# 11-MT7688AN_RF_Front_End.net
KiCad netlist of a schematic drawn in Altium Designer
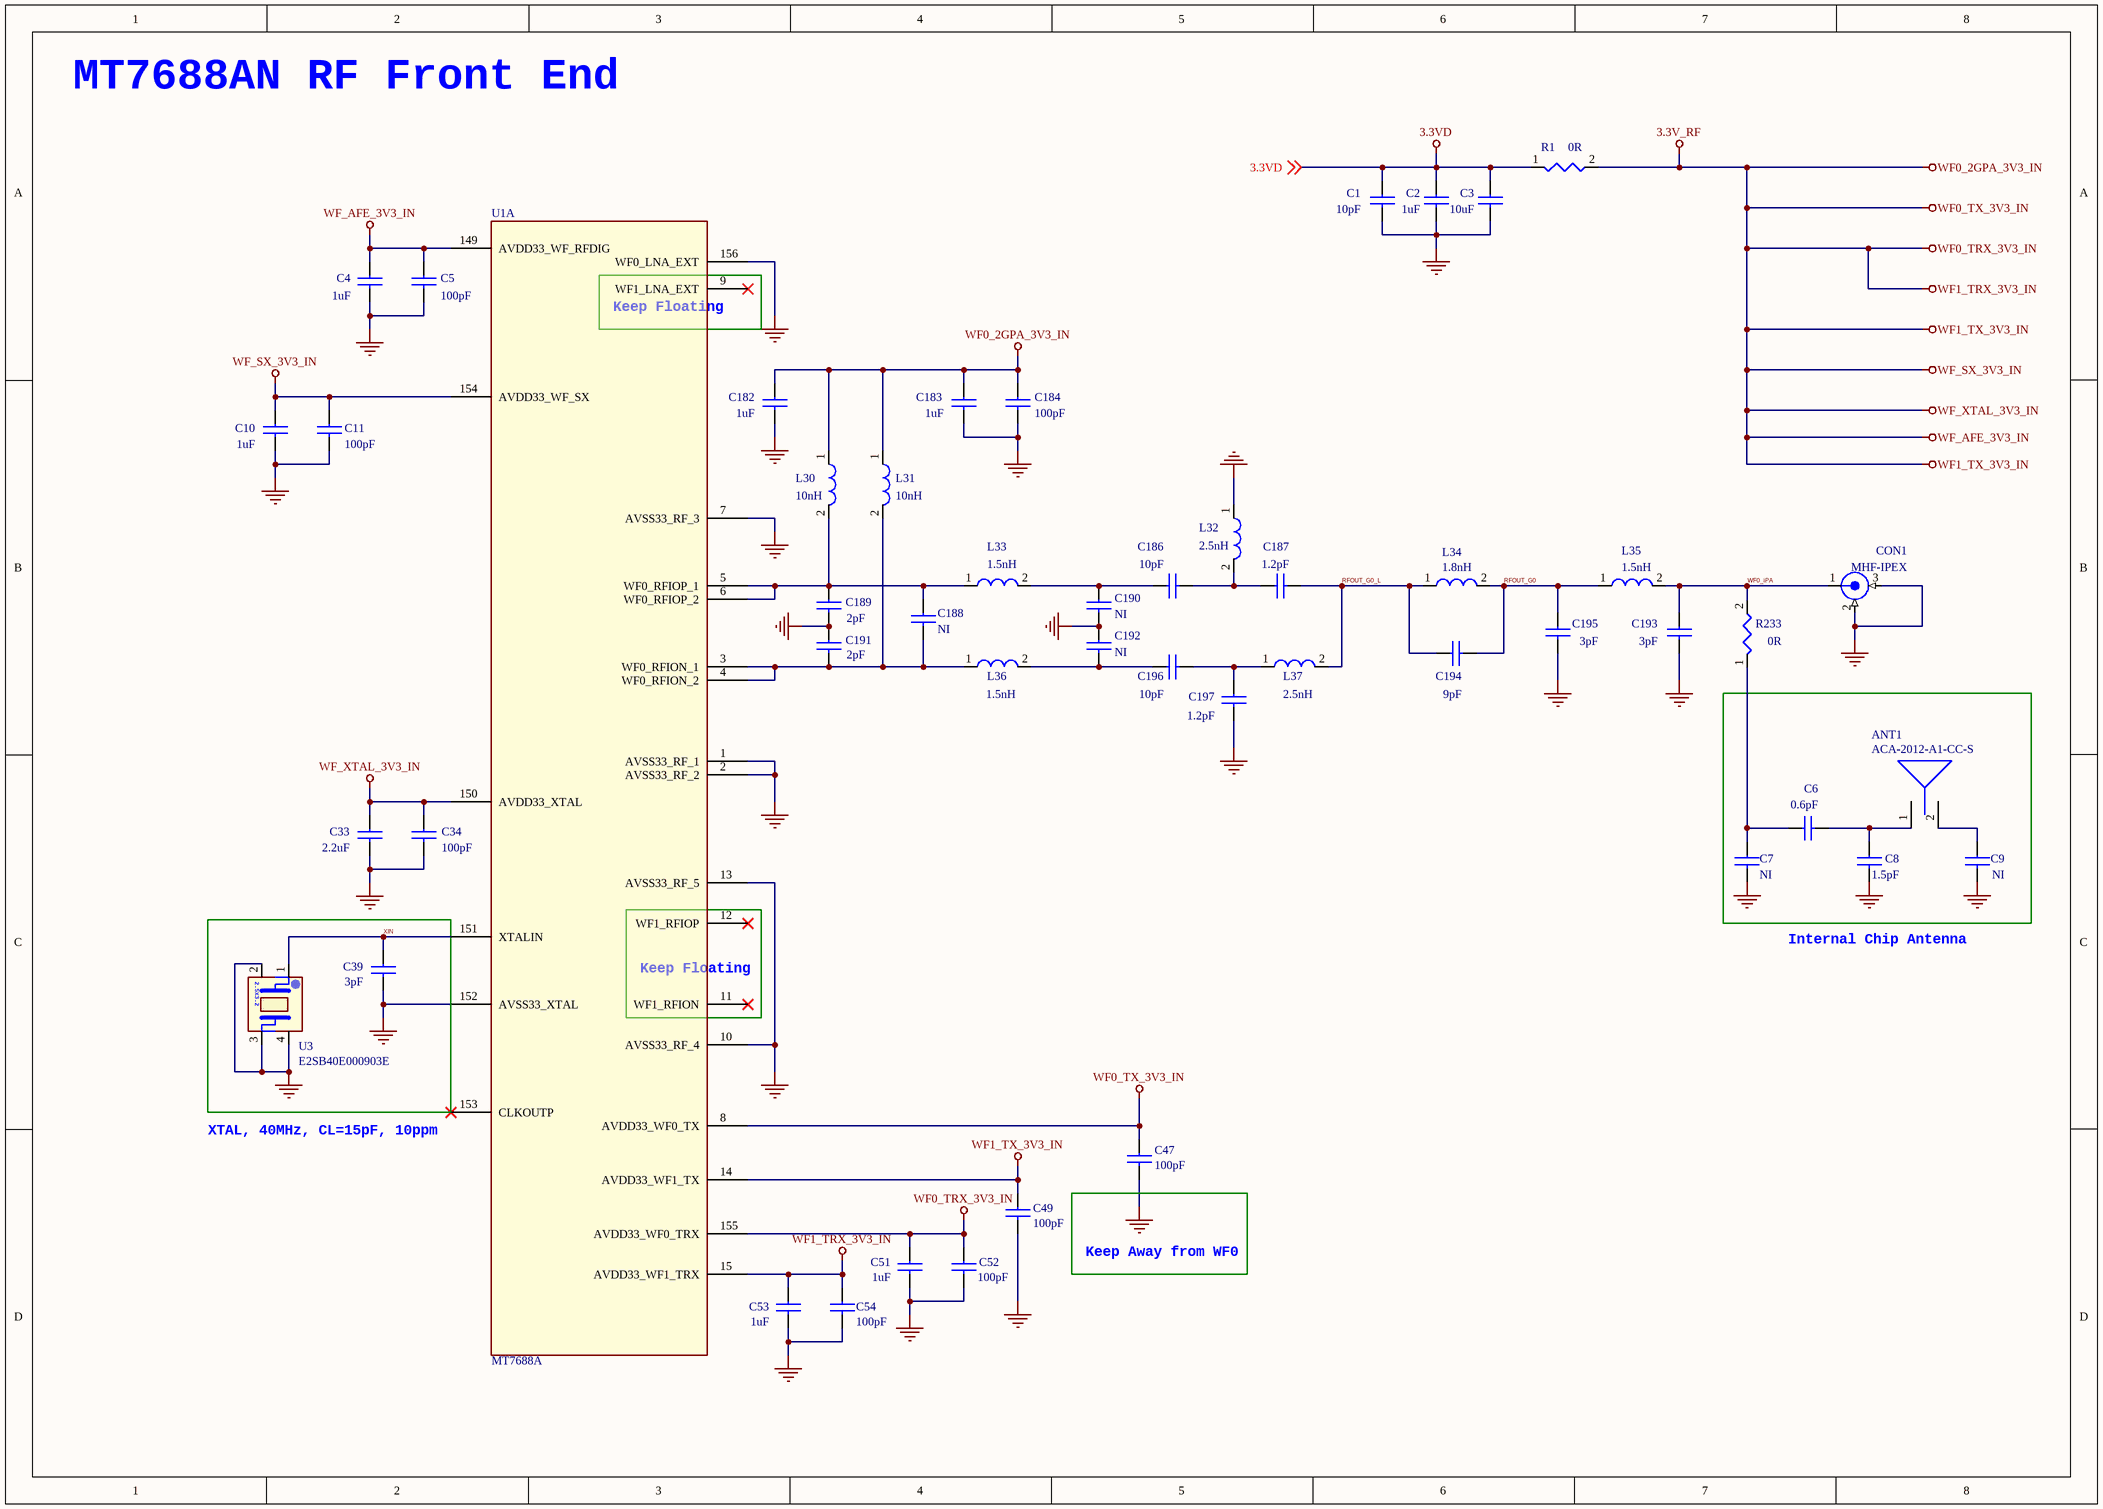
[diagram p0: 11-MT7688AN RF Front End.SchDoc]

(export (version "E")
  (design (tool "Eeschema 10.0.6"))
  (components
    (comp (ref "ANT1")
      (value "ACA-2012-A1-CC-S")
      (footprint "ACA-2012A")
      (libsource (lib "LinkIt Air+ (EK-7688AM+)") (part "Antenna_2012"))
    )
    (comp (ref "C1")
      (value "10pF")
      (footprint "RLC 0201 M35")
      (libsource (lib "LinkIt Air+ (EK-7688AM+)") (part "CAP NP"))
    )
    (comp (ref "C2")
      (value "1uF")
      (footprint "RLC 0201 M35")
      (libsource (lib "LinkIt Air+ (EK-7688AM+)") (part "CAP NP"))
    )
    (comp (ref "C3")
      (value "10uF")
      (footprint "RLC 0402 M35")
      (libsource (lib "LinkIt Air+ (EK-7688AM+)") (part "CAP NP"))
    )
    (comp (ref "C4")
      (value "1uF")
      (footprint "RLC 0201 M35")
      (libsource (lib "LinkIt Air+ (EK-7688AM+)") (part "CAP NP"))
    )
    (comp (ref "C5")
      (value "100pF")
      (footprint "RLC 0201 M35")
      (libsource (lib "LinkIt Air+ (EK-7688AM+)") (part "CAP NP"))
    )
    (comp (ref "C6")
      (value "0.6pF")
      (footprint "RLC 0201 M35")
      (libsource (lib "LinkIt Air+ (EK-7688AM+)") (part "CAP NP"))
    )
    (comp (ref "C7")
      (value "NI")
      (footprint "RLC 0201 M35")
      (libsource (lib "LinkIt Air+ (EK-7688AM+)") (part "CAP NP"))
    )
    (comp (ref "C8")
      (value "1.5pF")
      (footprint "RLC 0201 M35")
      (libsource (lib "LinkIt Air+ (EK-7688AM+)") (part "CAP NP"))
    )
    (comp (ref "C9")
      (value "NI")
      (footprint "RLC 0402 M35")
      (libsource (lib "LinkIt Air+ (EK-7688AM+)") (part "CAP NP"))
    )
    (comp (ref "C10")
      (value "1uF")
      (footprint "RLC 0201 M35")
      (libsource (lib "LinkIt Air+ (EK-7688AM+)") (part "CAP NP"))
    )
    (comp (ref "C11")
      (value "100pF")
      (footprint "RLC 0201 M35")
      (libsource (lib "LinkIt Air+ (EK-7688AM+)") (part "CAP NP"))
    )
    (comp (ref "C33")
      (value "2.2uF")
      (footprint "RLC 0402 M35")
      (libsource (lib "LinkIt Air+ (EK-7688AM+)") (part "CAP NP"))
    )
    (comp (ref "C34")
      (value "100pF")
      (footprint "RLC 0201 M35")
      (libsource (lib "LinkIt Air+ (EK-7688AM+)") (part "CAP NP"))
    )
    (comp (ref "C39")
      (value "3pF")
      (footprint "RLC 0201 M35")
      (libsource (lib "LinkIt Air+ (EK-7688AM+)") (part "CAP NP"))
    )
    (comp (ref "C47")
      (value "100pF")
      (footprint "RLC 0201 M35")
      (libsource (lib "LinkIt Air+ (EK-7688AM+)") (part "CAP NP"))
    )
    (comp (ref "C49")
      (value "100pF")
      (footprint "RLC 0201 M35")
      (libsource (lib "LinkIt Air+ (EK-7688AM+)") (part "CAP NP"))
    )
    (comp (ref "C51")
      (value "1uF")
      (footprint "RLC 0201 M35")
      (libsource (lib "LinkIt Air+ (EK-7688AM+)") (part "CAP NP"))
    )
    (comp (ref "C52")
      (value "100pF")
      (footprint "RLC 0201 M35")
      (libsource (lib "LinkIt Air+ (EK-7688AM+)") (part "CAP NP"))
    )
    (comp (ref "C53")
      (value "1uF")
      (footprint "RLC 0201 M35")
      (libsource (lib "LinkIt Air+ (EK-7688AM+)") (part "CAP NP"))
    )
    (comp (ref "C54")
      (value "100pF")
      (footprint "RLC 0201 M35")
      (libsource (lib "LinkIt Air+ (EK-7688AM+)") (part "CAP NP"))
    )
    (comp (ref "C182")
      (value "1uF")
      (footprint "RLC 0201 M35")
      (libsource (lib "LinkIt Air+ (EK-7688AM+)") (part "CAP NP"))
    )
    (comp (ref "C183")
      (value "1uF")
      (footprint "RLC 0201 M35")
      (libsource (lib "LinkIt Air+ (EK-7688AM+)") (part "CAP NP"))
    )
    (comp (ref "C184")
      (value "100pF")
      (footprint "RLC 0201 M35")
      (libsource (lib "LinkIt Air+ (EK-7688AM+)") (part "CAP NP"))
    )
    (comp (ref "C186")
      (value "10pF")
      (footprint "RLC 0201 M35")
      (libsource (lib "LinkIt Air+ (EK-7688AM+)") (part "CAP NP"))
    )
    (comp (ref "C187")
      (value "1.2pF")
      (footprint "RLC 0201 M35")
      (libsource (lib "LinkIt Air+ (EK-7688AM+)") (part "CAP NP"))
    )
    (comp (ref "C188")
      (value "NI")
      (footprint "RLC 0201 M35")
      (libsource (lib "LinkIt Air+ (EK-7688AM+)") (part "CAP NP"))
    )
    (comp (ref "C189")
      (value "2pF")
      (footprint "RLC 0201 M35")
      (libsource (lib "LinkIt Air+ (EK-7688AM+)") (part "CAP NP"))
    )
    (comp (ref "C190")
      (value "NI")
      (footprint "RLC 0201 M35")
      (libsource (lib "LinkIt Air+ (EK-7688AM+)") (part "CAP NP"))
    )
    (comp (ref "C191")
      (value "2pF")
      (footprint "RLC 0201 M35")
      (libsource (lib "LinkIt Air+ (EK-7688AM+)") (part "CAP NP"))
    )
    (comp (ref "C192")
      (value "NI")
      (footprint "RLC 0201 M35")
      (libsource (lib "LinkIt Air+ (EK-7688AM+)") (part "CAP NP"))
    )
    (comp (ref "C193")
      (value "3pF")
      (footprint "RLC 0201 M35")
      (libsource (lib "LinkIt Air+ (EK-7688AM+)") (part "CAP NP"))
    )
    (comp (ref "C194")
      (value "9pF")
      (footprint "RLC 0201 M35")
      (libsource (lib "LinkIt Air+ (EK-7688AM+)") (part "CAP NP"))
    )
    (comp (ref "C195")
      (value "3pF")
      (footprint "RLC 0201 M35")
      (libsource (lib "LinkIt Air+ (EK-7688AM+)") (part "CAP NP"))
    )
    (comp (ref "C196")
      (value "10pF")
      (footprint "RLC 0201 M35")
      (libsource (lib "LinkIt Air+ (EK-7688AM+)") (part "CAP NP"))
    )
    (comp (ref "C197")
      (value "1.2pF")
      (footprint "RLC 0201 M35")
      (libsource (lib "LinkIt Air+ (EK-7688AM+)") (part "CAP NP"))
    )
    (comp (ref "CON1")
      (value "MHF-IPEX")
      (footprint "I-PEX SOCKET")
      (libsource (lib "LinkIt Air+ (EK-7688AM+)") (part "SMA/UFLR"))
    )
    (comp (ref "L30")
      (value "10nH")
      (footprint "RLC 0201 M35")
      (libsource (lib "LinkIt Air+ (EK-7688AM+)") (part "L/0402"))
    )
    (comp (ref "L31")
      (value "10nH")
      (footprint "RLC 0201 M35")
      (libsource (lib "LinkIt Air+ (EK-7688AM+)") (part "L/0402"))
    )
    (comp (ref "L32")
      (value "2.5nH")
      (footprint "RLC 0201 M35")
      (libsource (lib "LinkIt Air+ (EK-7688AM+)") (part "L/0402"))
    )
    (comp (ref "L33")
      (value "1.5nH")
      (footprint "RLC 0201 M35")
      (description "LQP03TN1N5B02D")
      (libsource (lib "LinkIt Air+ (EK-7688AM+)") (part "L/0402"))
    )
    (comp (ref "L34")
      (value "1.8nH")
      (footprint "RLC 0201 M35")
      (libsource (lib "LinkIt Air+ (EK-7688AM+)") (part "L/0402"))
    )
    (comp (ref "L35")
      (value "1.5nH")
      (footprint "RLC 0201 M35")
      (description "LQP03TN1N5B02D")
      (libsource (lib "LinkIt Air+ (EK-7688AM+)") (part "L/0402"))
    )
    (comp (ref "L36")
      (value "1.5nH")
      (footprint "RLC 0201 M35")
      (description "LQP03TN1N5B02D")
      (libsource (lib "LinkIt Air+ (EK-7688AM+)") (part "L/0402"))
    )
    (comp (ref "L37")
      (value "2.5nH")
      (footprint "RLC 0201 M35")
      (libsource (lib "LinkIt Air+ (EK-7688AM+)") (part "L/0402"))
    )
    (comp (ref "R1")
      (value "0R")
      (footprint "RLC 0402 M35")
      (libsource (lib "LinkIt Air+ (EK-7688AM+)") (part "RES/0402_3"))
    )
    (comp (ref "R233")
      (value "0R")
      (footprint "RLC 0201 M35")
      (libsource (lib "LinkIt Air+ (EK-7688AM+)") (part "RES/0402_3"))
    )
    (comp (ref "U1")
      (value "MT7688A")
      (footprint "MT7628AN$2F$DRQFN156$2F$SMD$2F$P0.5$2F$12X12")
      (libsource (lib "LinkIt Air+ (EK-7688AM+)") (part "MT7620N-n_26"))
    )
    (comp (ref "U3")
      (value "E2SB40E000903E")
      (footprint "XTAL 2520 M50")
      (description "XTAL, 40MHz, CL=15pF, 10ppm, -30~+85C")
      (libsource (lib "LinkIt Air+ (EK-7688AM+)") (part "XTAL_3.2x2.5"))
    )
  )
  (nets
    (net (code "1") (name "/RFOUT_G0") (class "Default")
      (node (ref "C194") (pin "2") (pinfunction "2_2") (pintype "passive"))
      (node (ref "C195") (pin "1") (pinfunction "1_1") (pintype "passive"))
      (node (ref "L34") (pin "2") (pinfunction "2_2") (pintype "passive"))
      (node (ref "L35") (pin "1") (pinfunction "1_1") (pintype "passive"))
    )
    (net (code "2") (name "/RFOUT_G0_L") (class "Default")
      (node (ref "C187") (pin "2") (pinfunction "2_2") (pintype "passive"))
      (node (ref "C194") (pin "1") (pinfunction "1_1") (pintype "passive"))
      (node (ref "L34") (pin "1") (pinfunction "1_1") (pintype "passive"))
      (node (ref "L37") (pin "2") (pinfunction "2_2") (pintype "passive"))
    )
    (net (code "3") (name "/WF0_iPA") (class "Default")
      (node (ref "C193") (pin "1") (pinfunction "1_1") (pintype "passive"))
      (node (ref "CON1") (pin "1") (pinfunction "1_1") (pintype "passive"))
      (node (ref "L35") (pin "2") (pinfunction "2_2") (pintype "passive"))
      (node (ref "R233") (pin "2") (pinfunction "2_2") (pintype "passive"))
    )
    (net (code "4") (name "/XIN") (class "Default")
      (node (ref "C39") (pin "1") (pinfunction "1_1") (pintype "passive"))
      (node (ref "U1") (pin "151") (pinfunction "XTALIN_151") (pintype "passive"))
      (node (ref "U3") (pin "1") (pinfunction "X1_1") (pintype "passive"))
    )
    (net (code "5") (name "3.3VD") (class "Default")
      (node (ref "C1") (pin "1") (pinfunction "1_1") (pintype "passive"))
      (node (ref "C2") (pin "1") (pinfunction "1_1") (pintype "passive"))
      (node (ref "C3") (pin "1") (pinfunction "1_1") (pintype "passive"))
      (node (ref "R1") (pin "1") (pinfunction "1_1") (pintype "passive"))
    )
    (net (code "6") (name "3.3V_RF") (class "Default")
      (node (ref "C10") (pin "1") (pinfunction "1_1") (pintype "passive"))
      (node (ref "C11") (pin "1") (pinfunction "1_1") (pintype "passive"))
      (node (ref "C182") (pin "1") (pinfunction "1_1") (pintype "passive"))
      (node (ref "C183") (pin "1") (pinfunction "1_1") (pintype "passive"))
      (node (ref "C184") (pin "1") (pinfunction "1_1") (pintype "passive"))
      (node (ref "C33") (pin "1") (pinfunction "1_1") (pintype "passive"))
      (node (ref "C34") (pin "1") (pinfunction "1_1") (pintype "passive"))
      (node (ref "C4") (pin "1") (pinfunction "1_1") (pintype "passive"))
      (node (ref "C47") (pin "1") (pinfunction "1_1") (pintype "passive"))
      (node (ref "C49") (pin "1") (pinfunction "1_1") (pintype "passive"))
      (node (ref "C5") (pin "1") (pinfunction "1_1") (pintype "passive"))
      (node (ref "C51") (pin "1") (pinfunction "1_1") (pintype "passive"))
      (node (ref "C52") (pin "1") (pinfunction "1_1") (pintype "passive"))
      (node (ref "C53") (pin "1") (pinfunction "1_1") (pintype "passive"))
      (node (ref "C54") (pin "1") (pinfunction "1_1") (pintype "passive"))
      (node (ref "L30") (pin "1") (pinfunction "1_1") (pintype "passive"))
      (node (ref "L31") (pin "1") (pinfunction "1_1") (pintype "passive"))
      (node (ref "R1") (pin "2") (pinfunction "2_2") (pintype "passive"))
      (node (ref "U1") (pin "14") (pinfunction "AVDD33_WF1_TX_14") (pintype "power_in"))
      (node (ref "U1") (pin "149") (pinfunction "AVDD33_WF_RFDIG_149") (pintype "power_in"))
      (node (ref "U1") (pin "15") (pinfunction "AVDD33_WF1_TRX_15") (pintype "power_in"))
      (node (ref "U1") (pin "150") (pinfunction "AVDD33_XTAL_150") (pintype "power_in"))
      (node (ref "U1") (pin "154") (pinfunction "AVDD33_WF_SX_154") (pintype "power_in"))
      (node (ref "U1") (pin "155") (pinfunction "AVDD33_WF0_TRX_155") (pintype "power_in"))
      (node (ref "U1") (pin "8") (pinfunction "AVDD33_WF0_TX_8") (pintype "power_in"))
    )
    (net (code "7") (name "GND") (class "Default")
      (node (ref "C1") (pin "2") (pinfunction "2_2") (pintype "passive"))
      (node (ref "C10") (pin "2") (pinfunction "2_2") (pintype "passive"))
      (node (ref "C11") (pin "2") (pinfunction "2_2") (pintype "passive"))
      (node (ref "C182") (pin "2") (pinfunction "2_2") (pintype "passive"))
      (node (ref "C183") (pin "2") (pinfunction "2_2") (pintype "passive"))
      (node (ref "C184") (pin "2") (pinfunction "2_2") (pintype "passive"))
      (node (ref "C189") (pin "2") (pinfunction "2_2") (pintype "passive"))
      (node (ref "C190") (pin "2") (pinfunction "2_2") (pintype "passive"))
      (node (ref "C191") (pin "1") (pinfunction "1_1") (pintype "passive"))
      (node (ref "C192") (pin "1") (pinfunction "1_1") (pintype "passive"))
      (node (ref "C193") (pin "2") (pinfunction "2_2") (pintype "passive"))
      (node (ref "C195") (pin "2") (pinfunction "2_2") (pintype "passive"))
      (node (ref "C197") (pin "2") (pinfunction "2_2") (pintype "passive"))
      (node (ref "C2") (pin "2") (pinfunction "2_2") (pintype "passive"))
      (node (ref "C3") (pin "2") (pinfunction "2_2") (pintype "passive"))
      (node (ref "C33") (pin "2") (pinfunction "2_2") (pintype "passive"))
      (node (ref "C34") (pin "2") (pinfunction "2_2") (pintype "passive"))
      (node (ref "C39") (pin "2") (pinfunction "2_2") (pintype "passive"))
      (node (ref "C4") (pin "2") (pinfunction "2_2") (pintype "passive"))
      (node (ref "C47") (pin "2") (pinfunction "2_2") (pintype "passive"))
      (node (ref "C49") (pin "2") (pinfunction "2_2") (pintype "passive"))
      (node (ref "C5") (pin "2") (pinfunction "2_2") (pintype "passive"))
      (node (ref "C51") (pin "2") (pinfunction "2_2") (pintype "passive"))
      (node (ref "C52") (pin "2") (pinfunction "2_2") (pintype "passive"))
      (node (ref "C53") (pin "2") (pinfunction "2_2") (pintype "passive"))
      (node (ref "C54") (pin "2") (pinfunction "2_2") (pintype "passive"))
      (node (ref "C7") (pin "2") (pinfunction "2_2") (pintype "passive"))
      (node (ref "C8") (pin "2") (pinfunction "2_2") (pintype "passive"))
      (node (ref "C9") (pin "2") (pinfunction "2_2") (pintype "passive"))
      (node (ref "CON1") (pin "2") (pinfunction "2_2") (pintype "input"))
      (node (ref "CON1") (pin "3") (pinfunction "GNDA_3") (pintype "input"))
      (node (ref "L32") (pin "1") (pinfunction "1_1") (pintype "passive"))
      (node (ref "U1") (pin "1") (pinfunction "AVSS33_RF_1_1") (pintype "passive"))
      (node (ref "U1") (pin "10") (pinfunction "AVSS33_RF_4_10") (pintype "passive"))
      (node (ref "U1") (pin "13") (pinfunction "AVSS33_RF_5_13") (pintype "passive"))
      (node (ref "U1") (pin "152") (pinfunction "AVSS33_XTAL_152") (pintype "passive"))
      (node (ref "U1") (pin "156") (pinfunction "WF0_LNA_EXT_156") (pintype "passive"))
      (node (ref "U1") (pin "2") (pinfunction "AVSS33_RF_2_2") (pintype "passive"))
      (node (ref "U1") (pin "7") (pinfunction "AVSS33_RF_3_7") (pintype "passive"))
      (node (ref "U3") (pin "2") (pinfunction "NC_2") (pintype "passive"))
      (node (ref "U3") (pin "3") (pinfunction "X2_3") (pintype "passive"))
      (node (ref "U3") (pin "4") (pinfunction "NC_4") (pintype "passive"))
    )
    (net (code "8") (name "Net-(ANT1-IN)") (class "Default")
      (node (ref "ANT1") (pin "1") (pinfunction "IN_1") (pintype "passive"))
      (node (ref "C6") (pin "2") (pinfunction "2_2") (pintype "passive"))
      (node (ref "C8") (pin "1") (pinfunction "1_1") (pintype "passive"))
    )
    (net (code "9") (name "Net-(ANT1-OUT)") (class "Default")
      (node (ref "ANT1") (pin "2") (pinfunction "OUT_2") (pintype "passive"))
      (node (ref "C9") (pin "1") (pinfunction "1_1") (pintype "passive"))
    )
    (net (code "10") (name "Net-(C6-Pad1)") (class "Default")
      (node (ref "C6") (pin "1") (pinfunction "1_1") (pintype "passive"))
      (node (ref "C7") (pin "1") (pinfunction "1_1") (pintype "passive"))
      (node (ref "R233") (pin "1") (pinfunction "1_1") (pintype "passive"))
    )
    (net (code "11") (name "Net-(C186-Pad1)") (class "Default")
      (node (ref "C186") (pin "1") (pinfunction "1_1") (pintype "passive"))
      (node (ref "C190") (pin "1") (pinfunction "1_1") (pintype "passive"))
      (node (ref "L33") (pin "2") (pinfunction "2_2") (pintype "passive"))
    )
    (net (code "12") (name "Net-(C186-Pad2)") (class "Default")
      (node (ref "C186") (pin "2") (pinfunction "2_2") (pintype "passive"))
      (node (ref "C187") (pin "1") (pinfunction "1_1") (pintype "passive"))
      (node (ref "L32") (pin "2") (pinfunction "2_2") (pintype "passive"))
    )
    (net (code "13") (name "Net-(C192-Pad2)") (class "Default")
      (node (ref "C192") (pin "2") (pinfunction "2_2") (pintype "passive"))
      (node (ref "C196") (pin "1") (pinfunction "1_1") (pintype "passive"))
      (node (ref "L36") (pin "2") (pinfunction "2_2") (pintype "passive"))
    )
    (net (code "14") (name "Net-(C196-Pad2)") (class "Default")
      (node (ref "C196") (pin "2") (pinfunction "2_2") (pintype "passive"))
      (node (ref "C197") (pin "1") (pinfunction "1_1") (pintype "passive"))
      (node (ref "L37") (pin "1") (pinfunction "1_1") (pintype "passive"))
    )
    (net (code "15") (name "Net-(U1A-WF0_RFION_1)") (class "Default")
      (node (ref "C188") (pin "2") (pinfunction "2_2") (pintype "passive"))
      (node (ref "C191") (pin "2") (pinfunction "2_2") (pintype "passive"))
      (node (ref "L31") (pin "2") (pinfunction "2_2") (pintype "passive"))
      (node (ref "L36") (pin "1") (pinfunction "1_1") (pintype "passive"))
      (node (ref "U1") (pin "3") (pinfunction "WF0_RFION_1_3") (pintype "passive"))
      (node (ref "U1") (pin "4") (pinfunction "WF0_RFION_2_4") (pintype "passive"))
    )
    (net (code "16") (name "Net-(U1A-WF0_RFIOP_1)") (class "Default")
      (node (ref "C188") (pin "1") (pinfunction "1_1") (pintype "passive"))
      (node (ref "C189") (pin "1") (pinfunction "1_1") (pintype "passive"))
      (node (ref "L30") (pin "2") (pinfunction "2_2") (pintype "passive"))
      (node (ref "L33") (pin "1") (pinfunction "1_1") (pintype "passive"))
      (node (ref "U1") (pin "5") (pinfunction "WF0_RFIOP_1_5") (pintype "passive"))
      (node (ref "U1") (pin "6") (pinfunction "WF0_RFIOP_2_6") (pintype "passive"))
    )
    (net (code "17") (name "unconnected-(U1A-CLKOUTP-Pad153)") (class "Default")
      (node (ref "U1") (pin "153") (pinfunction "CLKOUTP_153") (pintype "passive+no_connect"))
    )
    (net (code "18") (name "unconnected-(U1A-WF1_LNA_EXT-Pad9)") (class "Default")
      (node (ref "U1") (pin "9") (pinfunction "WF1_LNA_EXT_9") (pintype "passive+no_connect"))
    )
    (net (code "19") (name "unconnected-(U1A-WF1_RFION-Pad11)") (class "Default")
      (node (ref "U1") (pin "11") (pinfunction "WF1_RFION_11") (pintype "passive+no_connect"))
    )
    (net (code "20") (name "unconnected-(U1A-WF1_RFIOP-Pad12)") (class "Default")
      (node (ref "U1") (pin "12") (pinfunction "WF1_RFIOP_12") (pintype "passive+no_connect"))
    )
  )
)
